# LazrFinal.net
KiCad netlist of a schematic drawn in EAGLE
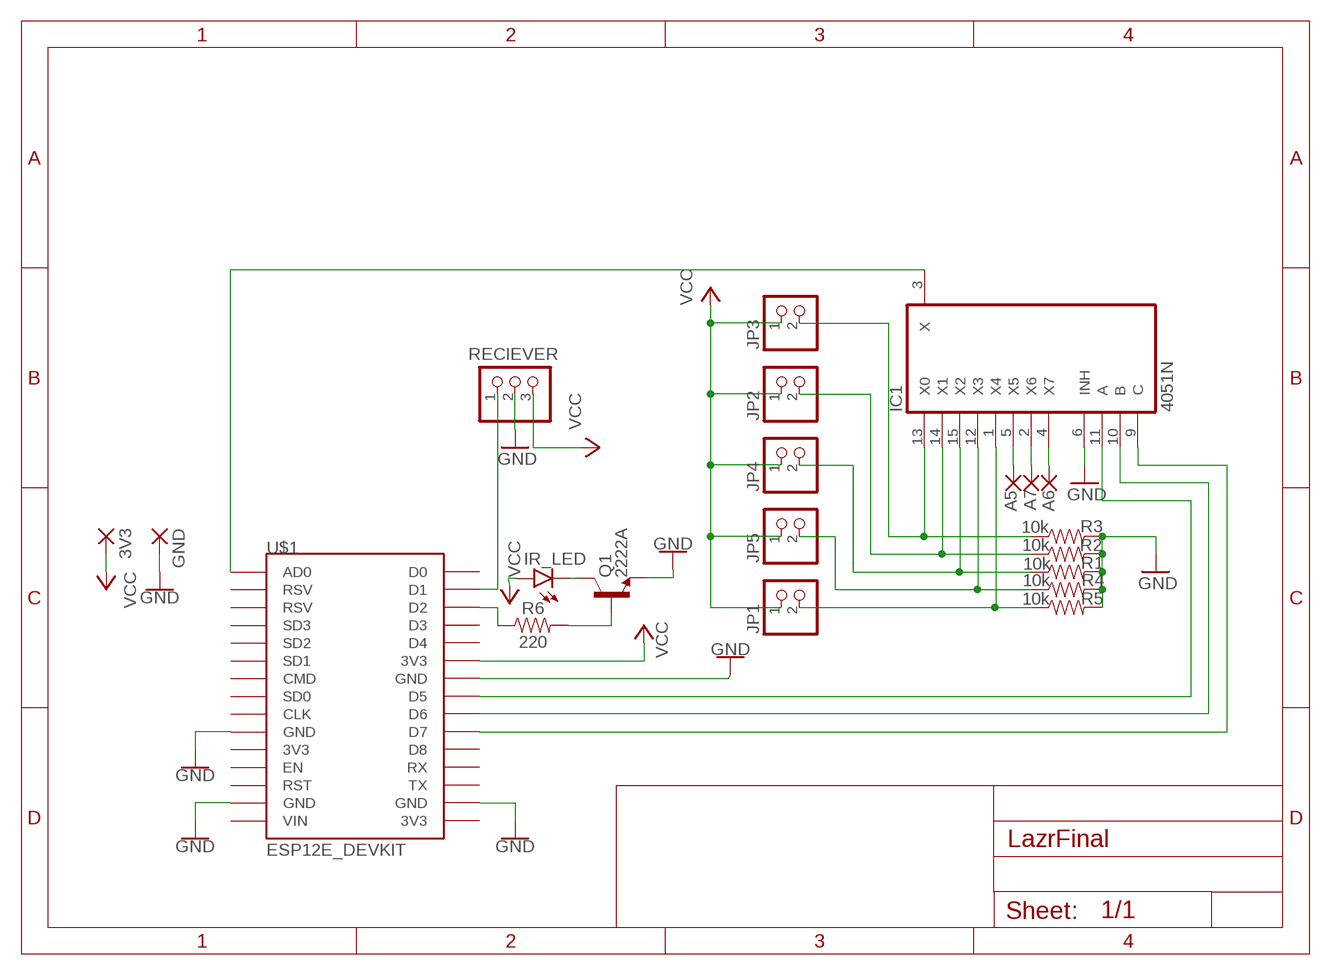
[diagram p0: schematic, sheet 1]

(export (version "E")
  (design (tool "Eeschema 10.0.6"))
  (components
    (comp (ref "3V3")
      (value "SMD5")
      (footprint "eagle-import:SMD2,54-5,08")
      (libsource (lib "eagle-import") (part "SMD5"))
    )
    (comp (ref "A5")
      (value "SMD2")
      (footprint "eagle-import:SMD1,27-2,54")
      (libsource (lib "eagle-import") (part "SMD2"))
    )
    (comp (ref "A6")
      (value "SMD2")
      (footprint "eagle-import:SMD1,27-2,54")
      (libsource (lib "eagle-import") (part "SMD2"))
    )
    (comp (ref "A7")
      (value "SMD2")
      (footprint "eagle-import:SMD1,27-2,54")
      (libsource (lib "eagle-import") (part "SMD2"))
    )
    (comp (ref "GND")
      (value "SMD5")
      (footprint "eagle-import:SMD2,54-5,08")
      (libsource (lib "eagle-import") (part "SMD5"))
    )
    (comp (ref "IC1")
      (value "4051N")
      (footprint "eagle-import:DIL16")
      (libsource (lib "eagle-import") (part "4051N"))
    )
    (comp (ref "IR_LED")
      (value "LED-IRTSAL6100")
      (footprint "eagle-import:LED_5MM")
      (libsource (lib "eagle-import") (part "LED-IRTSAL6100"))
    )
    (comp (ref "JP1")
      (value "PINHD-1X2")
      (footprint "eagle-import:1X02")
      (libsource (lib "eagle-import") (part "PINHD-1X2"))
    )
    (comp (ref "JP2")
      (value "PINHD-1X2")
      (footprint "eagle-import:1X02")
      (libsource (lib "eagle-import") (part "PINHD-1X2"))
    )
    (comp (ref "JP3")
      (value "PINHD-1X2")
      (footprint "eagle-import:1X02")
      (libsource (lib "eagle-import") (part "PINHD-1X2"))
    )
    (comp (ref "JP4")
      (value "PINHD-1X2")
      (footprint "eagle-import:1X02")
      (libsource (lib "eagle-import") (part "PINHD-1X2"))
    )
    (comp (ref "JP5")
      (value "PINHD-1X2")
      (footprint "eagle-import:1X02")
      (libsource (lib "eagle-import") (part "PINHD-1X2"))
    )
    (comp (ref "Q1")
      (value "2222A")
      (footprint "eagle-import:TO-92")
      (libsource (lib "eagle-import") (part "TRANS_NPN-2N3904"))
    )
    (comp (ref "R1")
      (value "10k")
      (footprint "eagle-import:AXIAL-0.3")
      (libsource (lib "eagle-import") (part "10KOHM-HORIZ-1/4W-5%"))
    )
    (comp (ref "R2")
      (value "10k")
      (footprint "eagle-import:AXIAL-0.3")
      (libsource (lib "eagle-import") (part "10KOHM-HORIZ-1/4W-5%"))
    )
    (comp (ref "R3")
      (value "10k")
      (footprint "eagle-import:AXIAL-0.3")
      (libsource (lib "eagle-import") (part "10KOHM-HORIZ-1/4W-5%"))
    )
    (comp (ref "R4")
      (value "10k")
      (footprint "eagle-import:AXIAL-0.3")
      (libsource (lib "eagle-import") (part "10KOHM-HORIZ-1/4W-5%"))
    )
    (comp (ref "R5")
      (value "10k")
      (footprint "eagle-import:AXIAL-0.3")
      (libsource (lib "eagle-import") (part "10KOHM-HORIZ-1/4W-5%"))
    )
    (comp (ref "R6")
      (value "220")
      (footprint "eagle-import:AXIAL-0.3")
      (libsource (lib "eagle-import") (part "1KOHM-HORIZ-1/4W-5%"))
    )
    (comp (ref "RECIEVER")
      (value "PINHD-1X3")
      (footprint "eagle-import:1X03")
      (libsource (lib "eagle-import") (part "PINHD-1X3"))
    )
    (comp (ref "U$1")
      (value "ESP12E_DEVKIT")
      (footprint "eagle-import:ESP12E_DEVKIT")
      (libsource (lib "eagle-import") (part "ESP12E_DEVKIT"))
    )
  )
  (nets
    (net (code "1") (name "GND") (class "Default")
      (node (ref "GND") (pin "1") (pinfunction "P_1") (pintype "passive"))
      (node (ref "IC1") (pin "6") (pinfunction "INH_6") (pintype "input"))
      (node (ref "Q1") (pin "1") (pinfunction "E_1") (pintype "passive"))
      (node (ref "R1") (pin "P$2") (pinfunction "2_P$2") (pintype "passive"))
      (node (ref "R2") (pin "P$2") (pinfunction "2_P$2") (pintype "passive"))
      (node (ref "R3") (pin "P$2") (pinfunction "2_P$2") (pintype "passive"))
      (node (ref "R4") (pin "P$2") (pinfunction "2_P$2") (pintype "passive"))
      (node (ref "R5") (pin "P$2") (pinfunction "2_P$2") (pintype "passive"))
      (node (ref "RECIEVER") (pin "2") (pinfunction "2_2") (pintype "passive"))
      (node (ref "U$1") (pin "GND@0") (pinfunction "GND_GND@0") (pintype "bidirectional"))
      (node (ref "U$1") (pin "GND@1") (pinfunction "GND_GND@1") (pintype "bidirectional"))
      (node (ref "U$1") (pin "GND@2") (pinfunction "GND_GND@2") (pintype "bidirectional"))
      (node (ref "U$1") (pin "GND@3") (pinfunction "GND_GND@3") (pintype "bidirectional"))
    )
    (net (code "2") (name "Net-(A5-P)") (class "Default")
      (node (ref "A5") (pin "1") (pinfunction "P_1") (pintype "passive"))
      (node (ref "IC1") (pin "5") (pinfunction "X5_5") (pintype "bidirectional"))
    )
    (net (code "3") (name "Net-(A6-P)") (class "Default")
      (node (ref "A6") (pin "1") (pinfunction "P_1") (pintype "passive"))
      (node (ref "IC1") (pin "4") (pinfunction "X7_4") (pintype "bidirectional"))
    )
    (net (code "4") (name "Net-(A7-P)") (class "Default")
      (node (ref "A7") (pin "1") (pinfunction "P_1") (pintype "passive"))
      (node (ref "IC1") (pin "2") (pinfunction "X6_2") (pintype "bidirectional"))
    )
    (net (code "5") (name "Net-(IC1A-A)") (class "Default")
      (node (ref "IC1") (pin "11") (pinfunction "A_11") (pintype "input"))
      (node (ref "U$1") (pin "D5") (pinfunction "D5_D5") (pintype "bidirectional"))
    )
    (net (code "6") (name "Net-(IC1A-B)") (class "Default")
      (node (ref "IC1") (pin "10") (pinfunction "B_10") (pintype "input"))
      (node (ref "U$1") (pin "D6") (pinfunction "D6_D6") (pintype "bidirectional"))
    )
    (net (code "7") (name "Net-(IC1A-C)") (class "Default")
      (node (ref "IC1") (pin "9") (pinfunction "C_9") (pintype "input"))
      (node (ref "U$1") (pin "D7") (pinfunction "D7_D7") (pintype "bidirectional"))
    )
    (net (code "8") (name "Net-(IC1A-X)") (class "Default")
      (node (ref "IC1") (pin "3") (pinfunction "X_3") (pintype "bidirectional"))
      (node (ref "U$1") (pin "AD0") (pinfunction "AD0_AD0") (pintype "bidirectional"))
    )
    (net (code "9") (name "Net-(IC1A-X0)") (class "Default")
      (node (ref "IC1") (pin "13") (pinfunction "X0_13") (pintype "bidirectional"))
      (node (ref "JP3") (pin "2") (pinfunction "2_2") (pintype "passive"))
      (node (ref "R3") (pin "P$1") (pinfunction "1_P$1") (pintype "passive"))
    )
    (net (code "10") (name "Net-(IC1A-X1)") (class "Default")
      (node (ref "IC1") (pin "14") (pinfunction "X1_14") (pintype "bidirectional"))
      (node (ref "JP2") (pin "2") (pinfunction "2_2") (pintype "passive"))
      (node (ref "R2") (pin "P$1") (pinfunction "1_P$1") (pintype "passive"))
    )
    (net (code "11") (name "Net-(IC1A-X2)") (class "Default")
      (node (ref "IC1") (pin "15") (pinfunction "X2_15") (pintype "bidirectional"))
      (node (ref "JP4") (pin "2") (pinfunction "2_2") (pintype "passive"))
      (node (ref "R1") (pin "P$1") (pinfunction "1_P$1") (pintype "passive"))
    )
    (net (code "12") (name "Net-(IC1A-X3)") (class "Default")
      (node (ref "IC1") (pin "12") (pinfunction "X3_12") (pintype "bidirectional"))
      (node (ref "JP5") (pin "2") (pinfunction "2_2") (pintype "passive"))
      (node (ref "R4") (pin "P$1") (pinfunction "1_P$1") (pintype "passive"))
    )
    (net (code "13") (name "Net-(IC1A-X4)") (class "Default")
      (node (ref "IC1") (pin "1") (pinfunction "X4_1") (pintype "bidirectional"))
      (node (ref "JP1") (pin "2") (pinfunction "2_2") (pintype "passive"))
      (node (ref "R5") (pin "P$1") (pinfunction "1_P$1") (pintype "passive"))
    )
    (net (code "14") (name "Net-(IR_LED-C)") (class "Default")
      (node (ref "IR_LED") (pin "K") (pinfunction "C_K") (pintype "passive"))
      (node (ref "Q1") (pin "3") (pinfunction "C_3") (pintype "passive"))
    )
    (net (code "15") (name "Net-(Q1-B)") (class "Default")
      (node (ref "Q1") (pin "2") (pinfunction "B_2") (pintype "passive"))
      (node (ref "R6") (pin "P$2") (pinfunction "2_P$2") (pintype "passive"))
    )
    (net (code "16") (name "Net-(R6-1)") (class "Default")
      (node (ref "R6") (pin "P$1") (pinfunction "1_P$1") (pintype "passive"))
      (node (ref "U$1") (pin "D2") (pinfunction "D2_D2") (pintype "bidirectional"))
    )
    (net (code "17") (name "Net-(RECIEVER-Pad1)") (class "Default")
      (node (ref "RECIEVER") (pin "1") (pinfunction "1_1") (pintype "passive"))
      (node (ref "U$1") (pin "D1") (pinfunction "D1_D1") (pintype "bidirectional"))
    )
    (net (code "18") (name "VCC") (class "Default")
      (node (ref "3V3") (pin "1") (pinfunction "P_1") (pintype "passive"))
      (node (ref "IR_LED") (pin "A") (pinfunction "A_A") (pintype "passive"))
      (node (ref "JP1") (pin "1") (pinfunction "1_1") (pintype "passive"))
      (node (ref "JP2") (pin "1") (pinfunction "1_1") (pintype "passive"))
      (node (ref "JP3") (pin "1") (pinfunction "1_1") (pintype "passive"))
      (node (ref "JP4") (pin "1") (pinfunction "1_1") (pintype "passive"))
      (node (ref "JP5") (pin "1") (pinfunction "1_1") (pintype "passive"))
      (node (ref "RECIEVER") (pin "3") (pinfunction "3_3") (pintype "passive"))
      (node (ref "U$1") (pin "3V3@1") (pinfunction "3V3_3V3@1") (pintype "bidirectional"))
    )
    (net (code "19") (name "unconnected-(U$1-3V3-Pad3V3@0)") (class "Default")
      (node (ref "U$1") (pin "3V3@0") (pinfunction "3V3_3V3@0") (pintype "bidirectional"))
    )
    (net (code "20") (name "unconnected-(U$1-3V3-Pad3V3@2)") (class "Default")
      (node (ref "U$1") (pin "3V3@2") (pinfunction "3V3_3V3@2") (pintype "bidirectional"))
    )
    (net (code "21") (name "unconnected-(U$1-PadCLK)") (class "Default")
      (node (ref "U$1") (pin "CLK") (pinfunction "CLK_CLK") (pintype "bidirectional"))
    )
    (net (code "22") (name "unconnected-(U$1-PadCMD)") (class "Default")
      (node (ref "U$1") (pin "CMD") (pinfunction "CMD_CMD") (pintype "bidirectional"))
    )
    (net (code "23") (name "unconnected-(U$1-PadD0)") (class "Default")
      (node (ref "U$1") (pin "D0") (pinfunction "D0_D0") (pintype "bidirectional"))
    )
    (net (code "24") (name "unconnected-(U$1-PadD3)") (class "Default")
      (node (ref "U$1") (pin "D3") (pinfunction "D3_D3") (pintype "bidirectional"))
    )
    (net (code "25") (name "unconnected-(U$1-PadD4)") (class "Default")
      (node (ref "U$1") (pin "D4") (pinfunction "D4_D4") (pintype "bidirectional"))
    )
    (net (code "26") (name "unconnected-(U$1-PadD8)") (class "Default")
      (node (ref "U$1") (pin "D8") (pinfunction "D8_D8") (pintype "bidirectional"))
    )
    (net (code "27") (name "unconnected-(U$1-PadEN)") (class "Default")
      (node (ref "U$1") (pin "EN") (pinfunction "EN_EN") (pintype "bidirectional"))
    )
    (net (code "28") (name "unconnected-(U$1-PadRST)") (class "Default")
      (node (ref "U$1") (pin "RST") (pinfunction "RST_RST") (pintype "bidirectional"))
    )
    (net (code "29") (name "unconnected-(U$1-PadRX)") (class "Default")
      (node (ref "U$1") (pin "RX") (pinfunction "RX_RX") (pintype "bidirectional"))
    )
    (net (code "30") (name "unconnected-(U$1-PadSD0)") (class "Default")
      (node (ref "U$1") (pin "SD0") (pinfunction "SD0_SD0") (pintype "bidirectional"))
    )
    (net (code "31") (name "unconnected-(U$1-PadSD1)") (class "Default")
      (node (ref "U$1") (pin "SD1") (pinfunction "SD1_SD1") (pintype "bidirectional"))
    )
    (net (code "32") (name "unconnected-(U$1-PadSD2)") (class "Default")
      (node (ref "U$1") (pin "SD2") (pinfunction "SD2_SD2") (pintype "bidirectional"))
    )
    (net (code "33") (name "unconnected-(U$1-PadSD3)") (class "Default")
      (node (ref "U$1") (pin "SD3") (pinfunction "SD3_SD3") (pintype "bidirectional"))
    )
    (net (code "34") (name "unconnected-(U$1-PadTX)") (class "Default")
      (node (ref "U$1") (pin "TX") (pinfunction "TX_TX") (pintype "bidirectional"))
    )
    (net (code "35") (name "unconnected-(U$1-PadVIN)") (class "Default")
      (node (ref "U$1") (pin "VIN") (pinfunction "VIN_VIN") (pintype "bidirectional"))
    )
    (net (code "36") (name "unconnected-(U$1-RSV-PadRSV@0)") (class "Default")
      (node (ref "U$1") (pin "RSV@0") (pinfunction "RSV_RSV@0") (pintype "bidirectional"))
    )
    (net (code "37") (name "unconnected-(U$1-RSV-PadRSV@1)") (class "Default")
      (node (ref "U$1") (pin "RSV@1") (pinfunction "RSV_RSV@1") (pintype "bidirectional"))
    )
  )
)
